# BB_SensorCape.net
KiCad netlist of a schematic drawn in EAGLE
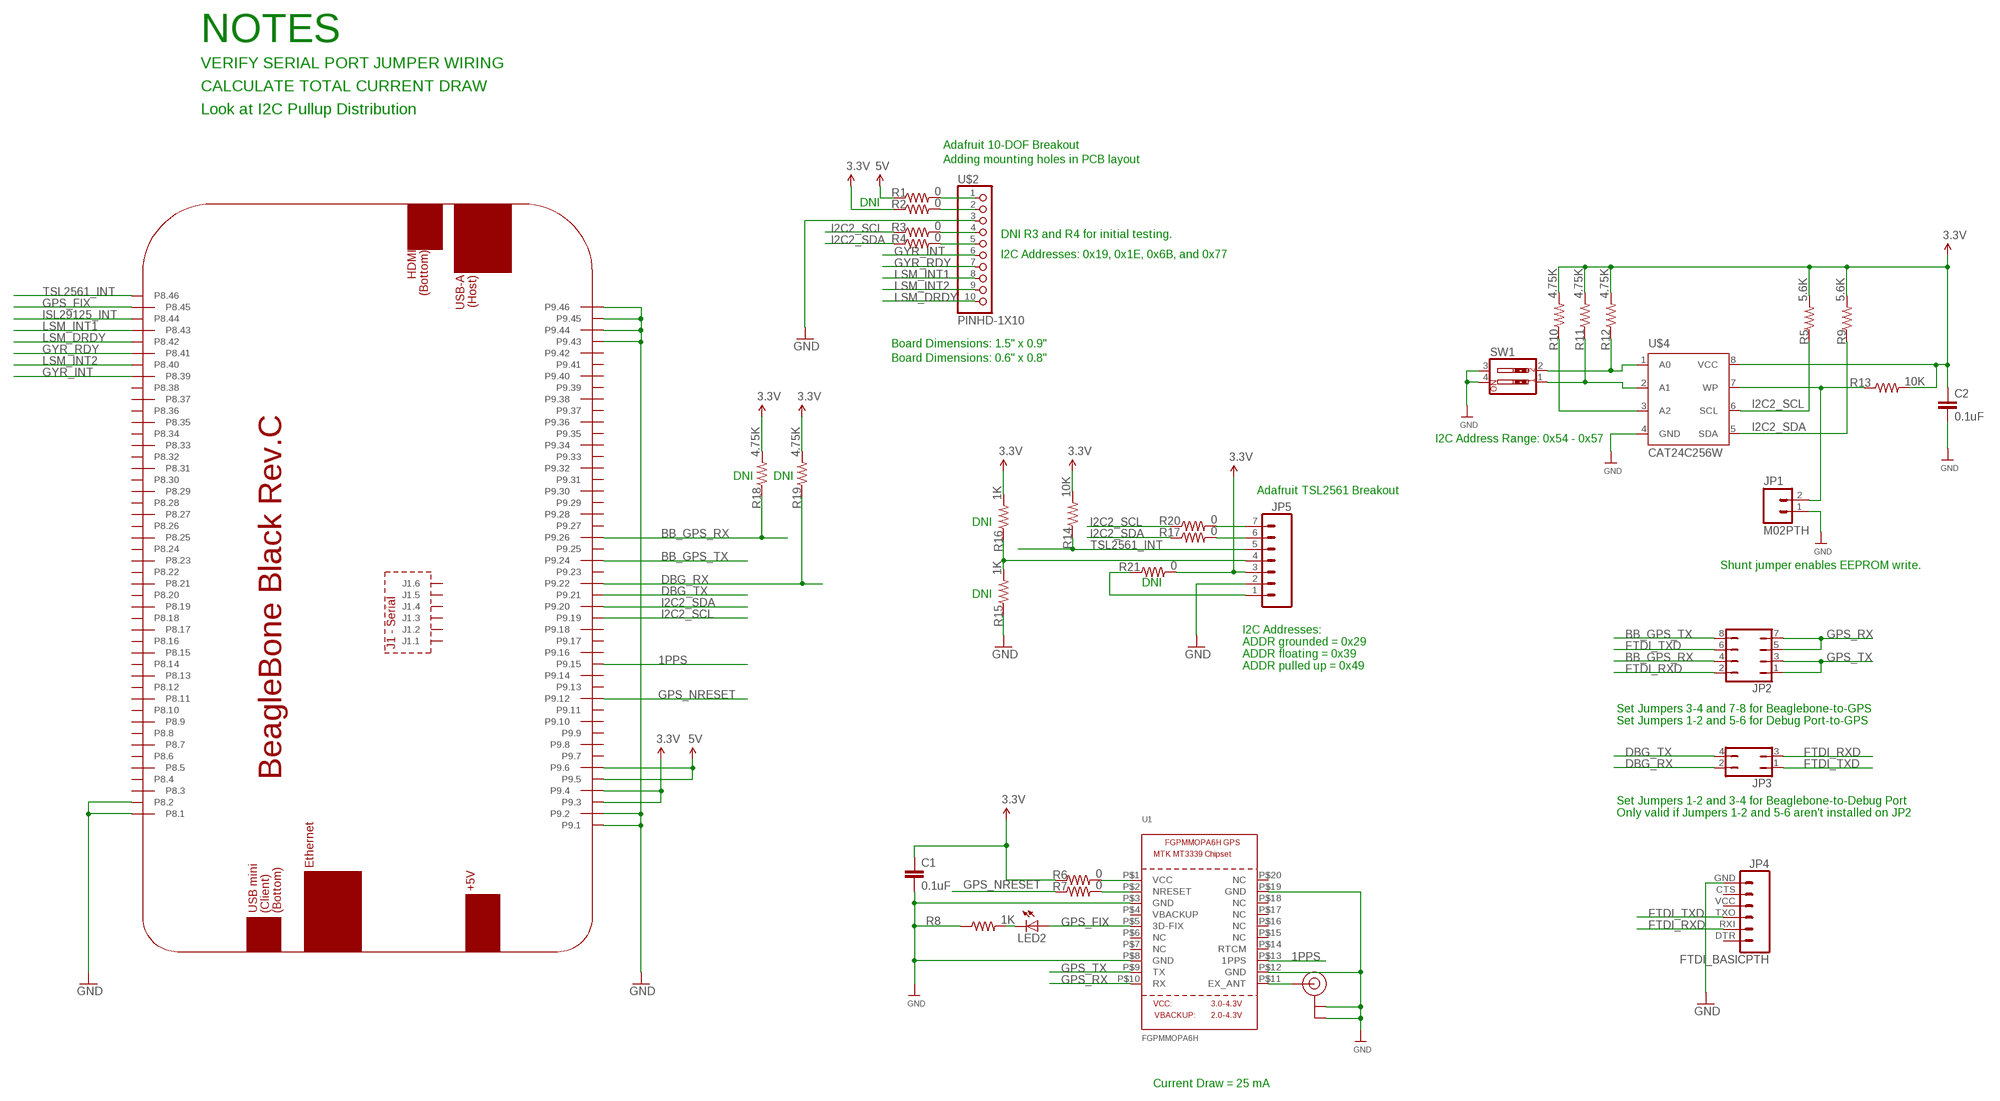
[diagram p0: schematic, sheet 1]

(export (version "E")
  (design (tool "Eeschema 10.0.6"))
  (components
    (comp (ref "C1")
      (value "0.1uF")
      (footprint "eagle-import:0603-CAP")
      (libsource (lib "eagle-import") (part "0.1UF-25V-5%(0603)"))
    )
    (comp (ref "C2")
      (value "0.1uF")
      (footprint "eagle-import:0603-CAP")
      (libsource (lib "eagle-import") (part "0.1UF-25V-5%(0603)"))
    )
    (comp (ref "JP1")
      (value "M02PTH")
      (footprint "eagle-import:1X02")
      (libsource (lib "eagle-import") (part "M02PTH"))
    )
    (comp (ref "JP2")
      (value "JP4Q")
      (footprint "eagle-import:JP4Q")
      (libsource (lib "eagle-import") (part "JP4Q"))
    )
    (comp (ref "JP3")
      (value "JP2Q")
      (footprint "eagle-import:JP2Q")
      (libsource (lib "eagle-import") (part "JP2Q"))
    )
    (comp (ref "JP4")
      (value "FTDI_BASICPTH")
      (footprint "eagle-import:FTDI_BASIC")
      (libsource (lib "eagle-import") (part "FTDI_BASICPTH"))
    )
    (comp (ref "JP5")
      (value "M07")
      (footprint "eagle-import:1X07")
      (libsource (lib "eagle-import") (part "M07"))
    )
    (comp (ref "LED2")
      (value "LEDCHIPLED_0805")
      (footprint "eagle-import:CHIPLED_0805")
      (libsource (lib "eagle-import") (part "LEDCHIPLED_0805"))
    )
    (comp (ref "PCB1")
      (value "BEAGLEBONE_BLACK")
      (footprint "eagle-import:BEAGLEBONE_BLACK")
      (libsource (lib "eagle-import") (part "BEAGLEBONE_BLACK"))
    )
    (comp (ref "R1")
      (value "0")
      (footprint "eagle-import:R0603")
      (libsource (lib "eagle-import") (part "R-US_R0603"))
    )
    (comp (ref "R2")
      (value "0")
      (footprint "eagle-import:R0603")
      (libsource (lib "eagle-import") (part "R-US_R0603"))
    )
    (comp (ref "R3")
      (value "0")
      (footprint "eagle-import:R0603")
      (libsource (lib "eagle-import") (part "R-US_R0603"))
    )
    (comp (ref "R4")
      (value "0")
      (footprint "eagle-import:R0603")
      (libsource (lib "eagle-import") (part "R-US_R0603"))
    )
    (comp (ref "R5")
      (value "5.6K")
      (footprint "eagle-import:R0603")
      (libsource (lib "eagle-import") (part "R-US_R0603"))
    )
    (comp (ref "R6")
      (value "0")
      (footprint "eagle-import:R0603")
      (libsource (lib "eagle-import") (part "R-US_R0603"))
    )
    (comp (ref "R7")
      (value "0")
      (footprint "eagle-import:R0603")
      (libsource (lib "eagle-import") (part "R-US_R0603"))
    )
    (comp (ref "R8")
      (value "1K")
      (footprint "eagle-import:R0603")
      (libsource (lib "eagle-import") (part "R-US_R0603"))
    )
    (comp (ref "R9")
      (value "5.6K")
      (footprint "eagle-import:R0603")
      (libsource (lib "eagle-import") (part "R-US_R0603"))
    )
    (comp (ref "R10")
      (value "4.75K")
      (footprint "eagle-import:R0603")
      (libsource (lib "eagle-import") (part "R-US_R0603"))
    )
    (comp (ref "R11")
      (value "4.75K")
      (footprint "eagle-import:R0603")
      (libsource (lib "eagle-import") (part "R-US_R0603"))
    )
    (comp (ref "R12")
      (value "4.75K")
      (footprint "eagle-import:R0603")
      (libsource (lib "eagle-import") (part "R-US_R0603"))
    )
    (comp (ref "R13")
      (value "10K")
      (footprint "eagle-import:R0603")
      (libsource (lib "eagle-import") (part "R-US_R0603"))
    )
    (comp (ref "R14")
      (value "10K")
      (footprint "eagle-import:R0603")
      (libsource (lib "eagle-import") (part "R-US_R0603"))
    )
    (comp (ref "R15")
      (value "1K")
      (footprint "eagle-import:R0603")
      (libsource (lib "eagle-import") (part "R-US_R0603"))
    )
    (comp (ref "R16")
      (value "1K")
      (footprint "eagle-import:R0603")
      (libsource (lib "eagle-import") (part "R-US_R0603"))
    )
    (comp (ref "R17")
      (value "0")
      (footprint "eagle-import:R0603")
      (libsource (lib "eagle-import") (part "R-US_R0603"))
    )
    (comp (ref "R18")
      (value "4.75K")
      (footprint "eagle-import:R0603")
      (libsource (lib "eagle-import") (part "R-US_R0603"))
    )
    (comp (ref "R19")
      (value "4.75K")
      (footprint "eagle-import:R0603")
      (libsource (lib "eagle-import") (part "R-US_R0603"))
    )
    (comp (ref "R20")
      (value "0")
      (footprint "eagle-import:R0603")
      (libsource (lib "eagle-import") (part "R-US_R0603"))
    )
    (comp (ref "R21")
      (value "0")
      (footprint "eagle-import:R0603")
      (libsource (lib "eagle-import") (part "R-US_R0603"))
    )
    (comp (ref "SW1")
      (value "SW_DIP-2-SMT-HALFSIZE")
      (footprint "eagle-import:DIPSWITCH-02-50MIL")
      (libsource (lib "eagle-import") (part "SW_DIP-2-SMT-HALFSIZE"))
    )
    (comp (ref "U$2")
      (value "PINHD-1X10")
      (footprint "eagle-import:1X10-BIG")
      (libsource (lib "eagle-import") (part "PINHD-1X10"))
    )
    (comp (ref "U$4")
      (value "CAT24C256W")
      (footprint "eagle-import:SO08")
      (libsource (lib "eagle-import") (part "CAT24C256W"))
    )
    (comp (ref "U$20")
      (value "U.FL")
      (footprint "eagle-import:U.FL")
      (libsource (lib "eagle-import") (part "U.FL"))
    )
    (comp (ref "U1")
      (value "FGPMMOPA6H")
      (footprint "eagle-import:FGPMMOPA6H")
      (libsource (lib "eagle-import") (part "GPS_FGPMMOPA6H"))
    )
  )
  (nets
    (net (code "1") (name "/1PPS") (class "Default")
      (node (ref "PCB1") (pin "P9.15") (pinfunction "P9.15_P9.15") (pintype "bidirectional"))
      (node (ref "U1") (pin "P$13") (pinfunction "1PPS_P$13") (pintype "bidirectional"))
    )
    (net (code "2") (name "/BB_GPS_RX") (class "Default")
      (node (ref "JP2") (pin "4") (pinfunction "4_4") (pintype "passive"))
      (node (ref "PCB1") (pin "P9.26") (pinfunction "P9.26_P9.26") (pintype "bidirectional"))
      (node (ref "R18") (pin "1") (pinfunction "1_1") (pintype "passive"))
    )
    (net (code "3") (name "/BB_GPS_TX") (class "Default")
      (node (ref "JP2") (pin "8") (pinfunction "8_8") (pintype "passive"))
      (node (ref "PCB1") (pin "P9.24") (pinfunction "P9.24_P9.24") (pintype "bidirectional"))
    )
    (net (code "4") (name "/DBG_RX") (class "Default")
      (node (ref "JP3") (pin "2") (pinfunction "2_2") (pintype "passive"))
      (node (ref "PCB1") (pin "P9.22") (pinfunction "P9.22_P9.22") (pintype "bidirectional"))
      (node (ref "R19") (pin "1") (pinfunction "1_1") (pintype "passive"))
    )
    (net (code "5") (name "/DBG_TX") (class "Default")
      (node (ref "JP3") (pin "4") (pinfunction "4_4") (pintype "passive"))
      (node (ref "PCB1") (pin "P9.21") (pinfunction "P9.21_P9.21") (pintype "bidirectional"))
    )
    (net (code "6") (name "/FTDI_RXD") (class "Default")
      (node (ref "JP2") (pin "2") (pinfunction "2_2") (pintype "passive"))
      (node (ref "JP3") (pin "3") (pinfunction "3_3") (pintype "passive"))
      (node (ref "JP4") (pin "RXI") (pinfunction "2_RXI") (pintype "passive"))
    )
    (net (code "7") (name "/FTDI_TXD") (class "Default")
      (node (ref "JP2") (pin "6") (pinfunction "6_6") (pintype "passive"))
      (node (ref "JP3") (pin "1") (pinfunction "1_1") (pintype "passive"))
      (node (ref "JP4") (pin "TXO") (pinfunction "3_TXO") (pintype "passive"))
    )
    (net (code "8") (name "/GPS_FIX") (class "Default")
      (node (ref "LED2") (pin "A") (pinfunction "A_A") (pintype "passive"))
      (node (ref "PCB1") (pin "P8.45") (pinfunction "P8.45_P8.45") (pintype "bidirectional"))
      (node (ref "U1") (pin "P$5") (pinfunction "3D-FIX_P$5") (pintype "bidirectional"))
    )
    (net (code "9") (name "/GPS_NRESET") (class "Default")
      (node (ref "PCB1") (pin "P9.12") (pinfunction "P9.12_P9.12") (pintype "bidirectional"))
      (node (ref "R7") (pin "1") (pinfunction "1_1") (pintype "passive"))
    )
    (net (code "10") (name "/GPS_RX") (class "Default")
      (node (ref "JP2") (pin "5") (pinfunction "5_5") (pintype "passive"))
      (node (ref "JP2") (pin "7") (pinfunction "7_7") (pintype "passive"))
      (node (ref "U1") (pin "P$10") (pinfunction "RX_P$10") (pintype "bidirectional"))
    )
    (net (code "11") (name "/GPS_TX") (class "Default")
      (node (ref "JP2") (pin "1") (pinfunction "1_1") (pintype "passive"))
      (node (ref "JP2") (pin "3") (pinfunction "3_3") (pintype "passive"))
      (node (ref "U1") (pin "P$9") (pinfunction "TX_P$9") (pintype "bidirectional"))
    )
    (net (code "12") (name "/GYR_INT") (class "Default")
      (node (ref "PCB1") (pin "P8.39") (pinfunction "P8.39_P8.39") (pintype "bidirectional"))
      (node (ref "U$2") (pin "6") (pinfunction "6_6") (pintype "passive"))
    )
    (net (code "13") (name "/GYR_RDY") (class "Default")
      (node (ref "PCB1") (pin "P8.41") (pinfunction "P8.41_P8.41") (pintype "bidirectional"))
      (node (ref "U$2") (pin "7") (pinfunction "7_7") (pintype "passive"))
    )
    (net (code "14") (name "/I2C2_SCL") (class "Default")
      (node (ref "PCB1") (pin "P9.19") (pinfunction "P9.19_P9.19") (pintype "bidirectional"))
      (node (ref "R20") (pin "1") (pinfunction "1_1") (pintype "passive"))
      (node (ref "R3") (pin "1") (pinfunction "1_1") (pintype "passive"))
      (node (ref "R5") (pin "1") (pinfunction "1_1") (pintype "passive"))
      (node (ref "U$4") (pin "6") (pinfunction "SCL_6") (pintype "bidirectional"))
    )
    (net (code "15") (name "/I2C2_SDA") (class "Default")
      (node (ref "PCB1") (pin "P9.20") (pinfunction "P9.20_P9.20") (pintype "bidirectional"))
      (node (ref "R17") (pin "1") (pinfunction "1_1") (pintype "passive"))
      (node (ref "R4") (pin "1") (pinfunction "1_1") (pintype "passive"))
      (node (ref "R9") (pin "1") (pinfunction "1_1") (pintype "passive"))
      (node (ref "U$4") (pin "5") (pinfunction "SDA_5") (pintype "bidirectional"))
    )
    (net (code "16") (name "/ISL29125_INT") (class "Default")
      (node (ref "PCB1") (pin "P8.44") (pinfunction "P8.44_P8.44") (pintype "bidirectional"))
    )
    (net (code "17") (name "/LSM_DRDY") (class "Default")
      (node (ref "PCB1") (pin "P8.42") (pinfunction "P8.42_P8.42") (pintype "bidirectional"))
      (node (ref "U$2") (pin "10") (pinfunction "10_10") (pintype "passive"))
    )
    (net (code "18") (name "/LSM_INT1") (class "Default")
      (node (ref "PCB1") (pin "P8.43") (pinfunction "P8.43_P8.43") (pintype "bidirectional"))
      (node (ref "U$2") (pin "8") (pinfunction "8_8") (pintype "passive"))
    )
    (net (code "19") (name "/LSM_INT2") (class "Default")
      (node (ref "PCB1") (pin "P8.40") (pinfunction "P8.40_P8.40") (pintype "bidirectional"))
      (node (ref "U$2") (pin "9") (pinfunction "9_9") (pintype "passive"))
    )
    (net (code "20") (name "/TSL2561_INT") (class "Default")
      (node (ref "JP5") (pin "5") (pinfunction "5_5") (pintype "passive"))
      (node (ref "PCB1") (pin "P8.46") (pinfunction "P8.46_P8.46") (pintype "bidirectional"))
      (node (ref "R14") (pin "1") (pinfunction "1_1") (pintype "passive"))
    )
    (net (code "21") (name "3.3V") (class "Default")
      (node (ref "C1") (pin "1") (pinfunction "1_1") (pintype "passive"))
      (node (ref "C2") (pin "1") (pinfunction "1_1") (pintype "passive"))
      (node (ref "JP5") (pin "3") (pinfunction "3_3") (pintype "passive"))
      (node (ref "PCB1") (pin "P9.3") (pinfunction "P9.3_P9.3") (pintype "bidirectional"))
      (node (ref "PCB1") (pin "P9.4") (pinfunction "P9.4_P9.4") (pintype "bidirectional"))
      (node (ref "R10") (pin "2") (pinfunction "2_2") (pintype "passive"))
      (node (ref "R11") (pin "2") (pinfunction "2_2") (pintype "passive"))
      (node (ref "R12") (pin "2") (pinfunction "2_2") (pintype "passive"))
      (node (ref "R13") (pin "2") (pinfunction "2_2") (pintype "passive"))
      (node (ref "R14") (pin "2") (pinfunction "2_2") (pintype "passive"))
      (node (ref "R16") (pin "2") (pinfunction "2_2") (pintype "passive"))
      (node (ref "R18") (pin "2") (pinfunction "2_2") (pintype "passive"))
      (node (ref "R19") (pin "2") (pinfunction "2_2") (pintype "passive"))
      (node (ref "R2") (pin "1") (pinfunction "1_1") (pintype "passive"))
      (node (ref "R21") (pin "2") (pinfunction "2_2") (pintype "passive"))
      (node (ref "R5") (pin "2") (pinfunction "2_2") (pintype "passive"))
      (node (ref "R6") (pin "1") (pinfunction "1_1") (pintype "passive"))
      (node (ref "R9") (pin "2") (pinfunction "2_2") (pintype "passive"))
      (node (ref "U$4") (pin "8") (pinfunction "VCC_8") (pintype "power_in"))
    )
    (net (code "22") (name "5V") (class "Default")
      (node (ref "PCB1") (pin "P9.5") (pinfunction "P9.5_P9.5") (pintype "bidirectional"))
      (node (ref "PCB1") (pin "P9.6") (pinfunction "P9.6_P9.6") (pintype "bidirectional"))
      (node (ref "R1") (pin "1") (pinfunction "1_1") (pintype "passive"))
    )
    (net (code "23") (name "GND") (class "Default")
      (node (ref "C1") (pin "2") (pinfunction "2_2") (pintype "passive"))
      (node (ref "C2") (pin "2") (pinfunction "2_2") (pintype "passive"))
      (node (ref "JP1") (pin "1") (pinfunction "1_1") (pintype "passive"))
      (node (ref "JP4") (pin "GND") (pinfunction "6_GND") (pintype "passive"))
      (node (ref "JP5") (pin "2") (pinfunction "2_2") (pintype "passive"))
      (node (ref "PCB1") (pin "P8.1") (pinfunction "P8.1_P8.1") (pintype "bidirectional"))
      (node (ref "PCB1") (pin "P8.2") (pinfunction "P8.2_P8.2") (pintype "bidirectional"))
      (node (ref "PCB1") (pin "P9.1") (pinfunction "P9.1_P9.1") (pintype "bidirectional"))
      (node (ref "PCB1") (pin "P9.2") (pinfunction "P9.2_P9.2") (pintype "bidirectional"))
      (node (ref "PCB1") (pin "P9.43") (pinfunction "P9.43_P9.43") (pintype "bidirectional"))
      (node (ref "PCB1") (pin "P9.44") (pinfunction "P9.44_P9.44") (pintype "bidirectional"))
      (node (ref "PCB1") (pin "P9.45") (pinfunction "P9.45_P9.45") (pintype "bidirectional"))
      (node (ref "PCB1") (pin "P9.46") (pinfunction "P9.46_P9.46") (pintype "bidirectional"))
      (node (ref "R15") (pin "1") (pinfunction "1_1") (pintype "passive"))
      (node (ref "R8") (pin "1") (pinfunction "1_1") (pintype "passive"))
      (node (ref "SW1") (pin "3") (pinfunction "3_3") (pintype "passive"))
      (node (ref "SW1") (pin "4") (pinfunction "4_4") (pintype "passive"))
      (node (ref "U$2") (pin "3") (pinfunction "3_3") (pintype "passive"))
      (node (ref "U$20") (pin "P$1") (pinfunction "GND_P$1") (pintype "bidirectional"))
      (node (ref "U$20") (pin "P$2") (pinfunction "GND_P$2") (pintype "bidirectional"))
      (node (ref "U$4") (pin "4") (pinfunction "GND_4") (pintype "power_in"))
      (node (ref "U1") (pin "P$12") (pinfunction "GND_P$12") (pintype "bidirectional"))
      (node (ref "U1") (pin "P$19") (pinfunction "GND_P$19") (pintype "bidirectional"))
      (node (ref "U1") (pin "P$3") (pinfunction "GND_P$3") (pintype "bidirectional"))
      (node (ref "U1") (pin "P$8") (pinfunction "GND_P$8") (pintype "bidirectional"))
    )
    (net (code "24") (name "Net-(JP5-Pad1)") (class "Default")
      (node (ref "JP5") (pin "1") (pinfunction "1_1") (pintype "passive"))
      (node (ref "R21") (pin "1") (pinfunction "1_1") (pintype "passive"))
    )
    (net (code "25") (name "Net-(JP5-Pad4)") (class "Default")
      (node (ref "JP5") (pin "4") (pinfunction "4_4") (pintype "passive"))
      (node (ref "R15") (pin "2") (pinfunction "2_2") (pintype "passive"))
      (node (ref "R16") (pin "1") (pinfunction "1_1") (pintype "passive"))
    )
    (net (code "26") (name "Net-(JP5-Pad6)") (class "Default")
      (node (ref "JP5") (pin "6") (pinfunction "6_6") (pintype "passive"))
      (node (ref "R17") (pin "2") (pinfunction "2_2") (pintype "passive"))
    )
    (net (code "27") (name "Net-(JP5-Pad7)") (class "Default")
      (node (ref "JP5") (pin "7") (pinfunction "7_7") (pintype "passive"))
      (node (ref "R20") (pin "2") (pinfunction "2_2") (pintype "passive"))
    )
    (net (code "28") (name "Net-(LED2-PadC)") (class "Default")
      (node (ref "LED2") (pin "C") (pinfunction "C_C") (pintype "passive"))
      (node (ref "R8") (pin "2") (pinfunction "2_2") (pintype "passive"))
    )
    (net (code "29") (name "Net-(R1-Pad2)") (class "Default")
      (node (ref "R1") (pin "2") (pinfunction "2_2") (pintype "passive"))
      (node (ref "U$2") (pin "1") (pinfunction "1_1") (pintype "passive"))
    )
    (net (code "30") (name "Net-(R2-Pad2)") (class "Default")
      (node (ref "R2") (pin "2") (pinfunction "2_2") (pintype "passive"))
      (node (ref "U$2") (pin "2") (pinfunction "2_2") (pintype "passive"))
    )
    (net (code "31") (name "Net-(R3-Pad2)") (class "Default")
      (node (ref "R3") (pin "2") (pinfunction "2_2") (pintype "passive"))
      (node (ref "U$2") (pin "4") (pinfunction "4_4") (pintype "passive"))
    )
    (net (code "32") (name "Net-(R4-Pad2)") (class "Default")
      (node (ref "R4") (pin "2") (pinfunction "2_2") (pintype "passive"))
      (node (ref "U$2") (pin "5") (pinfunction "5_5") (pintype "passive"))
    )
    (net (code "33") (name "Net-(U$4-A0)") (class "Default")
      (node (ref "R12") (pin "1") (pinfunction "1_1") (pintype "passive"))
      (node (ref "SW1") (pin "2") (pinfunction "2_2") (pintype "passive"))
      (node (ref "U$4") (pin "1") (pinfunction "A0_1") (pintype "input"))
    )
    (net (code "34") (name "Net-(U$4-A1)") (class "Default")
      (node (ref "R11") (pin "1") (pinfunction "1_1") (pintype "passive"))
      (node (ref "SW1") (pin "1") (pinfunction "1_1") (pintype "passive"))
      (node (ref "U$4") (pin "2") (pinfunction "A1_2") (pintype "input"))
    )
    (net (code "35") (name "Net-(U$4-A2)") (class "Default")
      (node (ref "R10") (pin "1") (pinfunction "1_1") (pintype "passive"))
      (node (ref "U$4") (pin "3") (pinfunction "A2_3") (pintype "input"))
    )
    (net (code "36") (name "Net-(U$4-WP)") (class "Default")
      (node (ref "JP1") (pin "2") (pinfunction "2_2") (pintype "passive"))
      (node (ref "R13") (pin "1") (pinfunction "1_1") (pintype "passive"))
      (node (ref "U$4") (pin "7") (pinfunction "WP_7") (pintype "input"))
    )
    (net (code "37") (name "Net-(U$20-SIGNAL)") (class "Default")
      (node (ref "U$20") (pin "P$3") (pinfunction "SIGNAL_P$3") (pintype "bidirectional"))
      (node (ref "U1") (pin "P$11") (pinfunction "EX_ANT_P$11") (pintype "bidirectional"))
    )
    (net (code "38") (name "Net-(U1-NRESET)") (class "Default")
      (node (ref "R7") (pin "2") (pinfunction "2_2") (pintype "passive"))
      (node (ref "U1") (pin "P$2") (pinfunction "NRESET_P$2") (pintype "bidirectional"))
    )
    (net (code "39") (name "Net-(U1-VCC)") (class "Default")
      (node (ref "R6") (pin "2") (pinfunction "2_2") (pintype "passive"))
      (node (ref "U1") (pin "P$1") (pinfunction "VCC_P$1") (pintype "bidirectional"))
    )
    (net (code "40") (name "unconnected-(JP4-1-PadDTR)") (class "Default")
      (node (ref "JP4") (pin "DTR") (pinfunction "1_DTR") (pintype "passive"))
    )
    (net (code "41") (name "unconnected-(JP4-4-PadVCC)") (class "Default")
      (node (ref "JP4") (pin "VCC") (pinfunction "4_VCC") (pintype "passive"))
    )
    (net (code "42") (name "unconnected-(JP4-5-PadCTS)") (class "Default")
      (node (ref "JP4") (pin "CTS") (pinfunction "5_CTS") (pintype "passive"))
    )
    (net (code "43") (name "unconnected-(PCB1-PadJ1.1)") (class "Default")
      (node (ref "PCB1") (pin "J1.1") (pinfunction "J1.1_J1.1") (pintype "bidirectional"))
    )
    (net (code "44") (name "unconnected-(PCB1-PadJ1.2)") (class "Default")
      (node (ref "PCB1") (pin "J1.2") (pinfunction "J1.2_J1.2") (pintype "bidirectional"))
    )
    (net (code "45") (name "unconnected-(PCB1-PadJ1.3)") (class "Default")
      (node (ref "PCB1") (pin "J1.3") (pinfunction "J1.3_J1.3") (pintype "bidirectional"))
    )
    (net (code "46") (name "unconnected-(PCB1-PadJ1.4)") (class "Default")
      (node (ref "PCB1") (pin "J1.4") (pinfunction "J1.4_J1.4") (pintype "bidirectional"))
    )
    (net (code "47") (name "unconnected-(PCB1-PadJ1.5)") (class "Default")
      (node (ref "PCB1") (pin "J1.5") (pinfunction "J1.5_J1.5") (pintype "bidirectional"))
    )
    (net (code "48") (name "unconnected-(PCB1-PadJ1.6)") (class "Default")
      (node (ref "PCB1") (pin "J1.6") (pinfunction "J1.6_J1.6") (pintype "bidirectional"))
    )
    (net (code "49") (name "unconnected-(PCB1-PadP8.3)") (class "Default")
      (node (ref "PCB1") (pin "P8.3") (pinfunction "P8.3_P8.3") (pintype "bidirectional"))
    )
    (net (code "50") (name "unconnected-(PCB1-PadP8.4)") (class "Default")
      (node (ref "PCB1") (pin "P8.4") (pinfunction "P8.4_P8.4") (pintype "bidirectional"))
    )
    (net (code "51") (name "unconnected-(PCB1-PadP8.5)") (class "Default")
      (node (ref "PCB1") (pin "P8.5") (pinfunction "P8.5_P8.5") (pintype "bidirectional"))
    )
    (net (code "52") (name "unconnected-(PCB1-PadP8.6)") (class "Default")
      (node (ref "PCB1") (pin "P8.6") (pinfunction "P8.6_P8.6") (pintype "bidirectional"))
    )
    (net (code "53") (name "unconnected-(PCB1-PadP8.7)") (class "Default")
      (node (ref "PCB1") (pin "P8.7") (pinfunction "P8.7_P8.7") (pintype "bidirectional"))
    )
    (net (code "54") (name "unconnected-(PCB1-PadP8.8)") (class "Default")
      (node (ref "PCB1") (pin "P8.8") (pinfunction "P8.8_P8.8") (pintype "bidirectional"))
    )
    (net (code "55") (name "unconnected-(PCB1-PadP8.9)") (class "Default")
      (node (ref "PCB1") (pin "P8.9") (pinfunction "P8.9_P8.9") (pintype "bidirectional"))
    )
    (net (code "56") (name "unconnected-(PCB1-PadP8.10)") (class "Default")
      (node (ref "PCB1") (pin "P8.10") (pinfunction "P8.10_P8.10") (pintype "bidirectional"))
    )
    (net (code "57") (name "unconnected-(PCB1-PadP8.11)") (class "Default")
      (node (ref "PCB1") (pin "P8.11") (pinfunction "P8.11_P8.11") (pintype "bidirectional"))
    )
    (net (code "58") (name "unconnected-(PCB1-PadP8.12)") (class "Default")
      (node (ref "PCB1") (pin "P8.12") (pinfunction "P8.12_P8.12") (pintype "bidirectional"))
    )
    (net (code "59") (name "unconnected-(PCB1-PadP8.13)") (class "Default")
      (node (ref "PCB1") (pin "P8.13") (pinfunction "P8.13_P8.13") (pintype "bidirectional"))
    )
    (net (code "60") (name "unconnected-(PCB1-PadP8.14)") (class "Default")
      (node (ref "PCB1") (pin "P8.14") (pinfunction "P8.14_P8.14") (pintype "bidirectional"))
    )
    (net (code "61") (name "unconnected-(PCB1-PadP8.15)") (class "Default")
      (node (ref "PCB1") (pin "P8.15") (pinfunction "P8.15_P8.15") (pintype "bidirectional"))
    )
    (net (code "62") (name "unconnected-(PCB1-PadP8.16)") (class "Default")
      (node (ref "PCB1") (pin "P8.16") (pinfunction "P8.16_P8.16") (pintype "bidirectional"))
    )
    (net (code "63") (name "unconnected-(PCB1-PadP8.17)") (class "Default")
      (node (ref "PCB1") (pin "P8.17") (pinfunction "P8.17_P8.17") (pintype "bidirectional"))
    )
    (net (code "64") (name "unconnected-(PCB1-PadP8.18)") (class "Default")
      (node (ref "PCB1") (pin "P8.18") (pinfunction "P8.18_P8.18") (pintype "bidirectional"))
    )
    (net (code "65") (name "unconnected-(PCB1-PadP8.19)") (class "Default")
      (node (ref "PCB1") (pin "P8.19") (pinfunction "P8.19_P8.19") (pintype "bidirectional"))
    )
    (net (code "66") (name "unconnected-(PCB1-PadP8.20)") (class "Default")
      (node (ref "PCB1") (pin "P8.20") (pinfunction "P8.20_P8.20") (pintype "bidirectional"))
    )
    (net (code "67") (name "unconnected-(PCB1-PadP8.21)") (class "Default")
      (node (ref "PCB1") (pin "P8.21") (pinfunction "P8.21_P8.21") (pintype "bidirectional"))
    )
    (net (code "68") (name "unconnected-(PCB1-PadP8.22)") (class "Default")
      (node (ref "PCB1") (pin "P8.22") (pinfunction "P8.22_P8.22") (pintype "bidirectional"))
    )
    (net (code "69") (name "unconnected-(PCB1-PadP8.23)") (class "Default")
      (node (ref "PCB1") (pin "P8.23") (pinfunction "P8.23_P8.23") (pintype "bidirectional"))
    )
    (net (code "70") (name "unconnected-(PCB1-PadP8.24)") (class "Default")
      (node (ref "PCB1") (pin "P8.24") (pinfunction "P8.24_P8.24") (pintype "bidirectional"))
    )
    (net (code "71") (name "unconnected-(PCB1-PadP8.25)") (class "Default")
      (node (ref "PCB1") (pin "P8.25") (pinfunction "P8.25_P8.25") (pintype "bidirectional"))
    )
    (net (code "72") (name "unconnected-(PCB1-PadP8.26)") (class "Default")
      (node (ref "PCB1") (pin "P8.26") (pinfunction "P8.26_P8.26") (pintype "bidirectional"))
    )
    (net (code "73") (name "unconnected-(PCB1-PadP8.27)") (class "Default")
      (node (ref "PCB1") (pin "P8.27") (pinfunction "P8.27_P8.27") (pintype "bidirectional"))
    )
    (net (code "74") (name "unconnected-(PCB1-PadP8.28)") (class "Default")
      (node (ref "PCB1") (pin "P8.28") (pinfunction "P8.28_P8.28") (pintype "bidirectional"))
    )
    (net (code "75") (name "unconnected-(PCB1-PadP8.29)") (class "Default")
      (node (ref "PCB1") (pin "P8.29") (pinfunction "P8.29_P8.29") (pintype "bidirectional"))
    )
    (net (code "76") (name "unconnected-(PCB1-PadP8.30)") (class "Default")
      (node (ref "PCB1") (pin "P8.30") (pinfunction "P8.30_P8.30") (pintype "bidirectional"))
    )
    (net (code "77") (name "unconnected-(PCB1-PadP8.31)") (class "Default")
      (node (ref "PCB1") (pin "P8.31") (pinfunction "P8.31_P8.31") (pintype "bidirectional"))
    )
    (net (code "78") (name "unconnected-(PCB1-PadP8.32)") (class "Default")
      (node (ref "PCB1") (pin "P8.32") (pinfunction "P8.32_P8.32") (pintype "bidirectional"))
    )
    (net (code "79") (name "unconnected-(PCB1-PadP8.33)") (class "Default")
      (node (ref "PCB1") (pin "P8.33") (pinfunction "P8.33_P8.33") (pintype "bidirectional"))
    )
    (net (code "80") (name "unconnected-(PCB1-PadP8.34)") (class "Default")
      (node (ref "PCB1") (pin "P8.34") (pinfunction "P8.34_P8.34") (pintype "bidirectional"))
    )
    (net (code "81") (name "unconnected-(PCB1-PadP8.35)") (class "Default")
      (node (ref "PCB1") (pin "P8.35") (pinfunction "P8.35_P8.35") (pintype "bidirectional"))
    )
    (net (code "82") (name "unconnected-(PCB1-PadP8.36)") (class "Default")
      (node (ref "PCB1") (pin "P8.36") (pinfunction "P8.36_P8.36") (pintype "bidirectional"))
    )
    (net (code "83") (name "unconnected-(PCB1-PadP8.37)") (class "Default")
      (node (ref "PCB1") (pin "P8.37") (pinfunction "P8.37_P8.37") (pintype "bidirectional"))
    )
    (net (code "84") (name "unconnected-(PCB1-PadP8.38)") (class "Default")
      (node (ref "PCB1") (pin "P8.38") (pinfunction "P8.38_P8.38") (pintype "bidirectional"))
    )
    (net (code "85") (name "unconnected-(PCB1-PadP9.7)") (class "Default")
      (node (ref "PCB1") (pin "P9.7") (pinfunction "P9.7_P9.7") (pintype "bidirectional"))
    )
    (net (code "86") (name "unconnected-(PCB1-PadP9.8)") (class "Default")
      (node (ref "PCB1") (pin "P9.8") (pinfunction "P9.8_P9.8") (pintype "bidirectional"))
    )
    (net (code "87") (name "unconnected-(PCB1-PadP9.9)") (class "Default")
      (node (ref "PCB1") (pin "P9.9") (pinfunction "P9.9_P9.9") (pintype "bidirectional"))
    )
    (net (code "88") (name "unconnected-(PCB1-PadP9.10)") (class "Default")
      (node (ref "PCB1") (pin "P9.10") (pinfunction "P9.10_P9.10") (pintype "bidirectional"))
    )
    (net (code "89") (name "unconnected-(PCB1-PadP9.11)") (class "Default")
      (node (ref "PCB1") (pin "P9.11") (pinfunction "P9.11_P9.11") (pintype "bidirectional"))
    )
    (net (code "90") (name "unconnected-(PCB1-PadP9.13)") (class "Default")
      (node (ref "PCB1") (pin "P9.13") (pinfunction "P9.13_P9.13") (pintype "bidirectional"))
    )
    (net (code "91") (name "unconnected-(PCB1-PadP9.14)") (class "Default")
      (node (ref "PCB1") (pin "P9.14") (pinfunction "P9.14_P9.14") (pintype "bidirectional"))
    )
    (net (code "92") (name "unconnected-(PCB1-PadP9.16)") (class "Default")
      (node (ref "PCB1") (pin "P9.16") (pinfunction "P9.16_P9.16") (pintype "bidirectional"))
    )
    (net (code "93") (name "unconnected-(PCB1-PadP9.17)") (class "Default")
      (node (ref "PCB1") (pin "P9.17") (pinfunction "P9.17_P9.17") (pintype "bidirectional"))
    )
    (net (code "94") (name "unconnected-(PCB1-PadP9.18)") (class "Default")
      (node (ref "PCB1") (pin "P9.18") (pinfunction "P9.18_P9.18") (pintype "bidirectional"))
    )
    (net (code "95") (name "unconnected-(PCB1-PadP9.23)") (class "Default")
      (node (ref "PCB1") (pin "P9.23") (pinfunction "P9.23_P9.23") (pintype "bidirectional"))
    )
    (net (code "96") (name "unconnected-(PCB1-PadP9.25)") (class "Default")
      (node (ref "PCB1") (pin "P9.25") (pinfunction "P9.25_P9.25") (pintype "bidirectional"))
    )
    (net (code "97") (name "unconnected-(PCB1-PadP9.27)") (class "Default")
      (node (ref "PCB1") (pin "P9.27") (pinfunction "P9.27_P9.27") (pintype "bidirectional"))
    )
    (net (code "98") (name "unconnected-(PCB1-PadP9.28)") (class "Default")
      (node (ref "PCB1") (pin "P9.28") (pinfunction "P9.28_P9.28") (pintype "bidirectional"))
    )
    (net (code "99") (name "unconnected-(PCB1-PadP9.29)") (class "Default")
      (node (ref "PCB1") (pin "P9.29") (pinfunction "P9.29_P9.29") (pintype "bidirectional"))
    )
    (net (code "100") (name "unconnected-(PCB1-PadP9.30)") (class "Default")
      (node (ref "PCB1") (pin "P9.30") (pinfunction "P9.30_P9.30") (pintype "bidirectional"))
    )
    (net (code "101") (name "unconnected-(PCB1-PadP9.31)") (class "Default")
      (node (ref "PCB1") (pin "P9.31") (pinfunction "P9.31_P9.31") (pintype "bidirectional"))
    )
    (net (code "102") (name "unconnected-(PCB1-PadP9.32)") (class "Default")
      (node (ref "PCB1") (pin "P9.32") (pinfunction "P9.32_P9.32") (pintype "bidirectional"))
    )
    (net (code "103") (name "unconnected-(PCB1-PadP9.33)") (class "Default")
      (node (ref "PCB1") (pin "P9.33") (pinfunction "P9.33_P9.33") (pintype "bidirectional"))
    )
    (net (code "104") (name "unconnected-(PCB1-PadP9.34)") (class "Default")
      (node (ref "PCB1") (pin "P9.34") (pinfunction "P9.34_P9.34") (pintype "bidirectional"))
    )
    (net (code "105") (name "unconnected-(PCB1-PadP9.35)") (class "Default")
      (node (ref "PCB1") (pin "P9.35") (pinfunction "P9.35_P9.35") (pintype "bidirectional"))
    )
    (net (code "106") (name "unconnected-(PCB1-PadP9.36)") (class "Default")
      (node (ref "PCB1") (pin "P9.36") (pinfunction "P9.36_P9.36") (pintype "bidirectional"))
    )
    (net (code "107") (name "unconnected-(PCB1-PadP9.37)") (class "Default")
      (node (ref "PCB1") (pin "P9.37") (pinfunction "P9.37_P9.37") (pintype "bidirectional"))
    )
    (net (code "108") (name "unconnected-(PCB1-PadP9.38)") (class "Default")
      (node (ref "PCB1") (pin "P9.38") (pinfunction "P9.38_P9.38") (pintype "bidirectional"))
    )
    (net (code "109") (name "unconnected-(PCB1-PadP9.39)") (class "Default")
      (node (ref "PCB1") (pin "P9.39") (pinfunction "P9.39_P9.39") (pintype "bidirectional"))
    )
    (net (code "110") (name "unconnected-(PCB1-PadP9.40)") (class "Default")
      (node (ref "PCB1") (pin "P9.40") (pinfunction "P9.40_P9.40") (pintype "bidirectional"))
    )
    (net (code "111") (name "unconnected-(PCB1-PadP9.41)") (class "Default")
      (node (ref "PCB1") (pin "P9.41") (pinfunction "P9.41_P9.41") (pintype "bidirectional"))
    )
    (net (code "112") (name "unconnected-(PCB1-PadP9.42)") (class "Default")
      (node (ref "PCB1") (pin "P9.42") (pinfunction "P9.42_P9.42") (pintype "bidirectional"))
    )
    (net (code "113") (name "unconnected-(U1-NC-PadP$6)") (class "Default")
      (node (ref "U1") (pin "P$6") (pinfunction "NC_P$6") (pintype "bidirectional"))
    )
    (net (code "114") (name "unconnected-(U1-NC-PadP$7)") (class "Default")
      (node (ref "U1") (pin "P$7") (pinfunction "NC_P$7") (pintype "bidirectional"))
    )
    (net (code "115") (name "unconnected-(U1-NC-PadP$15)") (class "Default")
      (node (ref "U1") (pin "P$15") (pinfunction "NC_P$15") (pintype "bidirectional"))
    )
    (net (code "116") (name "unconnected-(U1-NC-PadP$16)") (class "Default")
      (node (ref "U1") (pin "P$16") (pinfunction "NC_P$16") (pintype "bidirectional"))
    )
    (net (code "117") (name "unconnected-(U1-NC-PadP$17)") (class "Default")
      (node (ref "U1") (pin "P$17") (pinfunction "NC_P$17") (pintype "bidirectional"))
    )
    (net (code "118") (name "unconnected-(U1-NC-PadP$18)") (class "Default")
      (node (ref "U1") (pin "P$18") (pinfunction "NC_P$18") (pintype "bidirectional"))
    )
    (net (code "119") (name "unconnected-(U1-NC-PadP$20)") (class "Default")
      (node (ref "U1") (pin "P$20") (pinfunction "NC_P$20") (pintype "bidirectional"))
    )
    (net (code "120") (name "unconnected-(U1-RTCM-PadP$14)") (class "Default")
      (node (ref "U1") (pin "P$14") (pinfunction "RTCM_P$14") (pintype "bidirectional"))
    )
    (net (code "121") (name "unconnected-(U1-VBACKUP-PadP$4)") (class "Default")
      (node (ref "U1") (pin "P$4") (pinfunction "VBACKUP_P$4") (pintype "bidirectional"))
    )
  )
)
